# 01_MAIN.net
KiCad netlist of a schematic drawn in Altium Designer
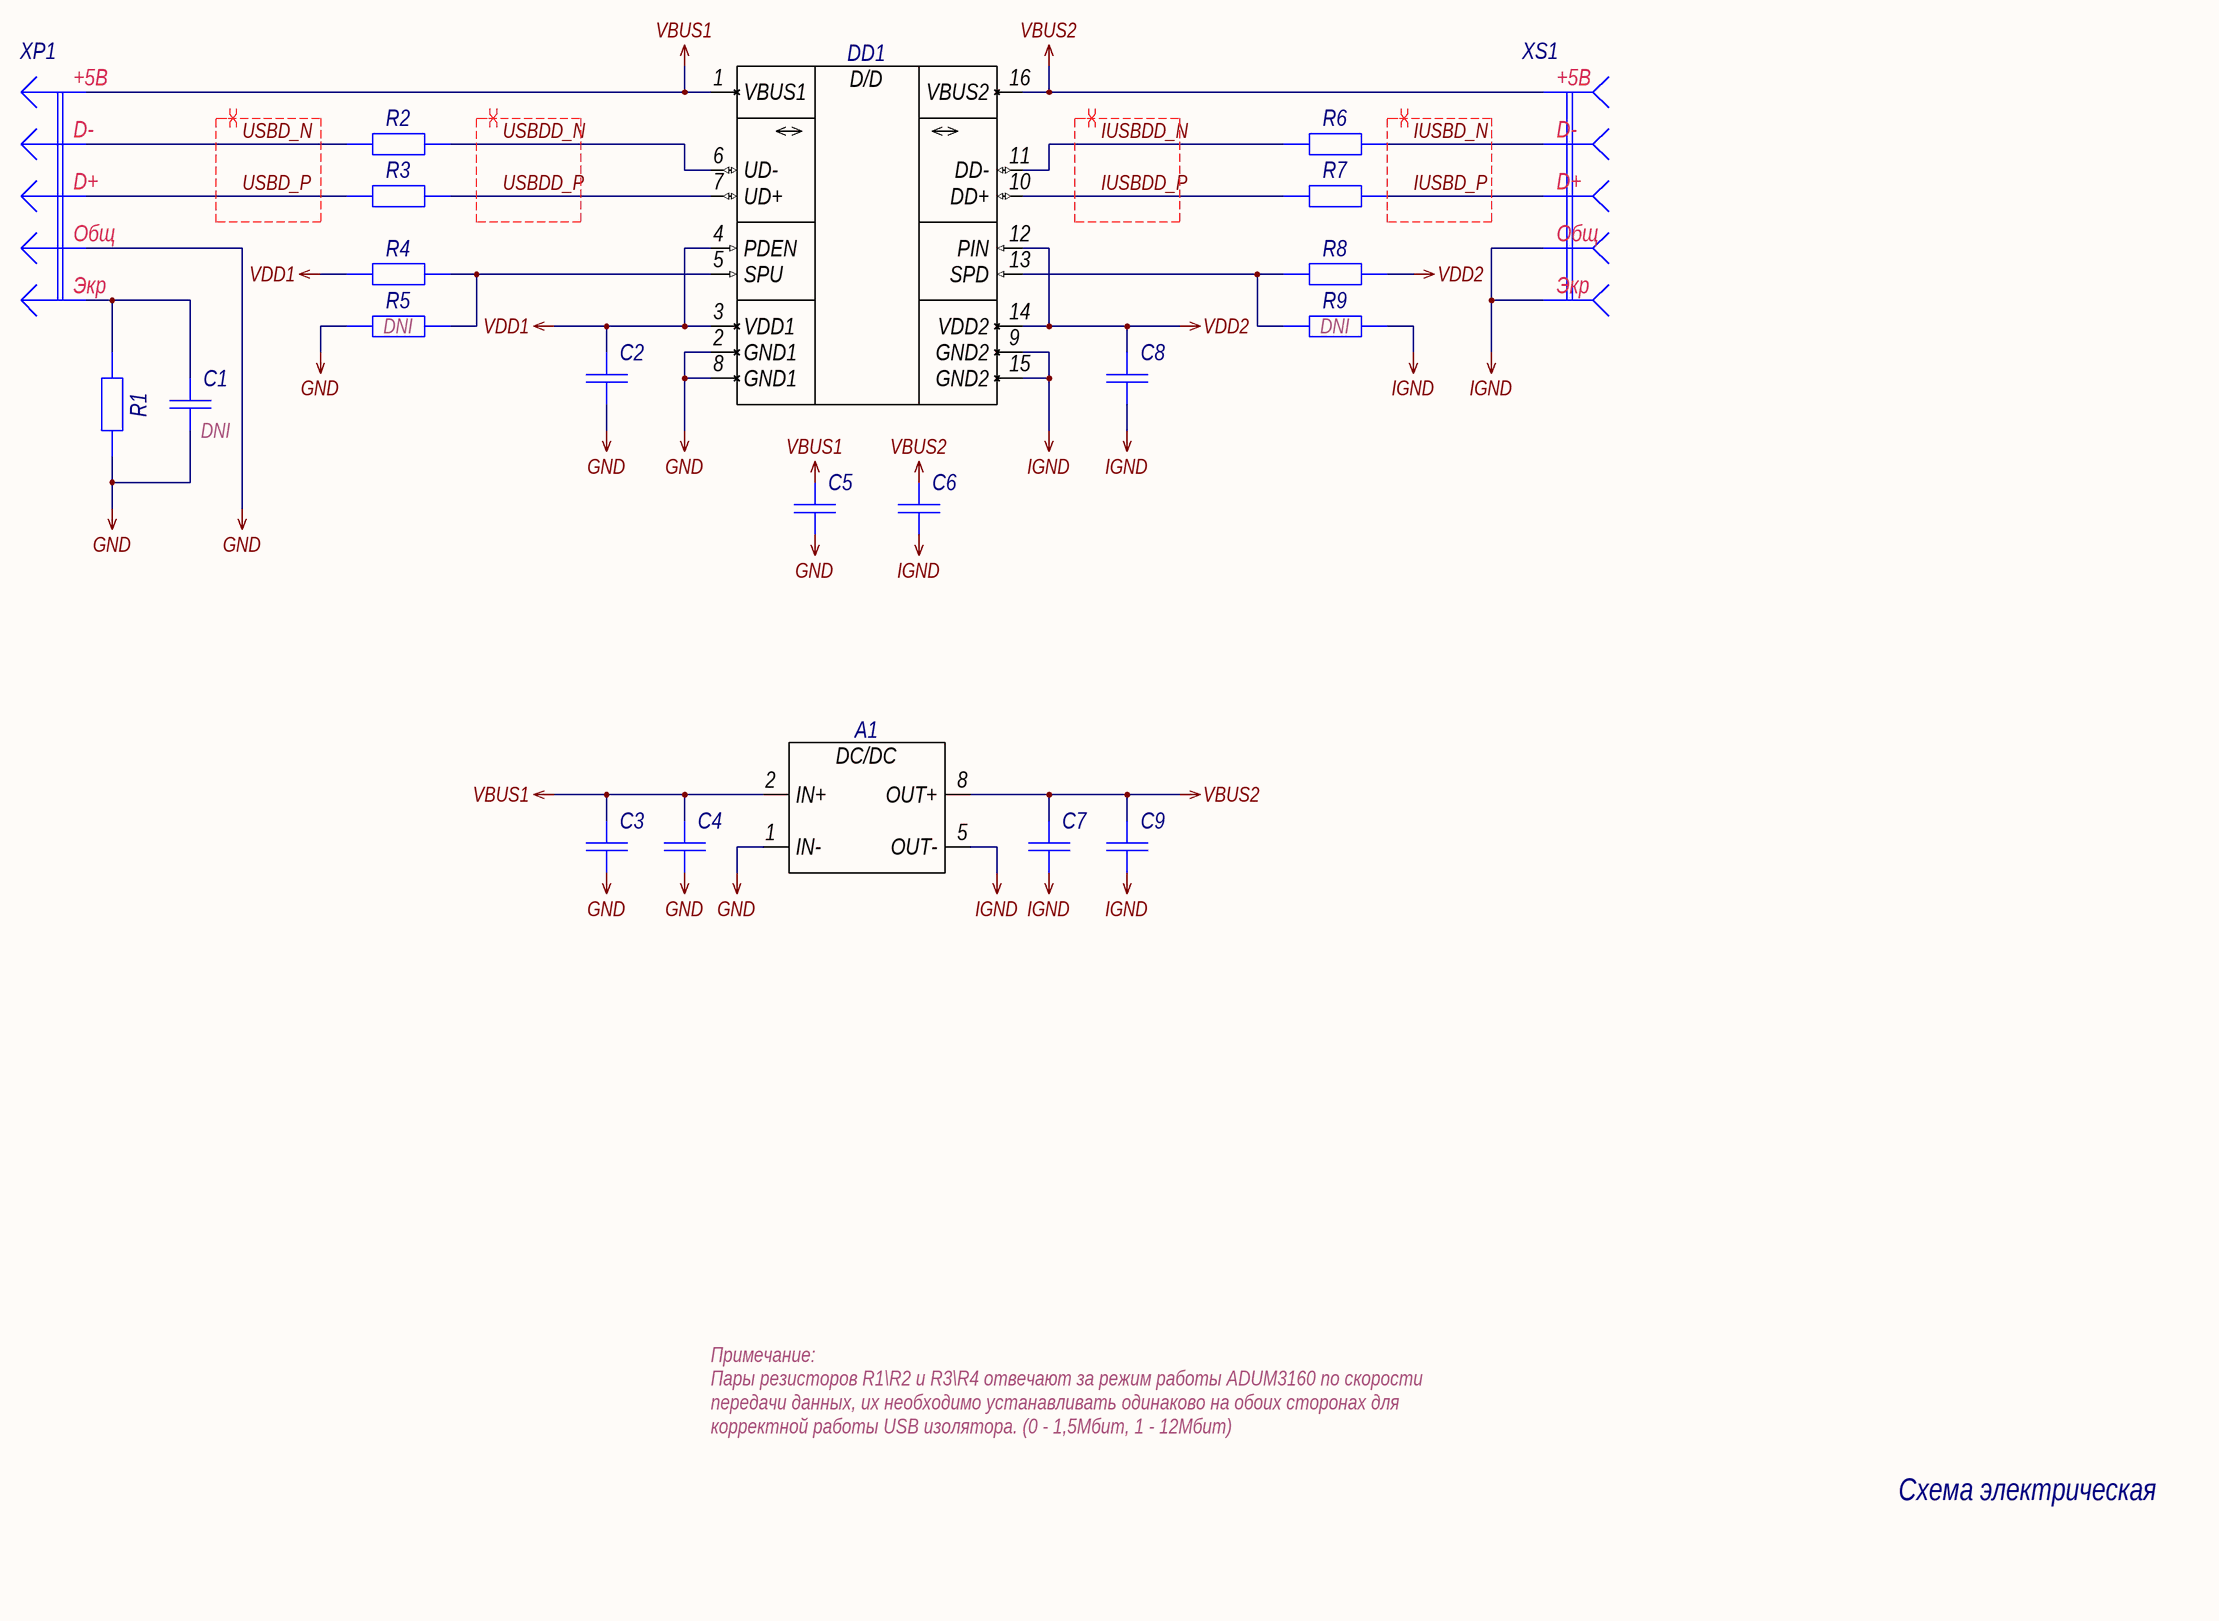
[diagram p0: 01_MAIN.SchDoc]

(export (version "E")
  (design (tool "Eeschema 10.0.6"))
  (components
    (comp (ref "A1")
      (value "AM1L-xxxxSH30-Series")
      (footprint "AM1L-xxxxSH30-Series")
      (fields
        (field (name "PART NUMBER") "AM1L-0505SH30-NZ")
        (field (name "MANUFACTURER") "Aimtec")
        (field (name "PUBLISHER") "Andrew Danich")
      )
      (libsource (lib "ADLib") (part "AM1L-xxxxSH30-Series"))
    )
    (comp (ref "C1")
      (value "Capacitor")
      (footprint "C0603_L")
      (fields
        (field (name "PART NUMBER") "GRM188R72A104KA35D")
        (field (name "VOLTAGE") "100V")
        (field (name "TOLERANCE") "±10%")
        (field (name "PUBLISHER") "Andrew Danich")
      )
      (libsource (lib "ADLib") (part "Capacitor"))
    )
    (comp (ref "C2")
      (value "Capacitor")
      (footprint "C0603_L")
      (fields
        (field (name "PART NUMBER") "GRM188R72A104KA35D")
        (field (name "VOLTAGE") "100V")
        (field (name "TOLERANCE") "±10%")
        (field (name "PUBLISHER") "Andrew Danich")
      )
      (libsource (lib "ADLib") (part "Capacitor"))
    )
    (comp (ref "C3")
      (value "Capacitor")
      (footprint "C0603_L")
      (fields
        (field (name "PART NUMBER") "GRM188R72A104KA35D")
        (field (name "VOLTAGE") "100V")
        (field (name "TOLERANCE") "±10%")
        (field (name "PUBLISHER") "Andrew Danich")
      )
      (libsource (lib "ADLib") (part "Capacitor"))
    )
    (comp (ref "C4")
      (value "Capacitor")
      (footprint "C0603_L")
      (fields
        (field (name "PART NUMBER") "GRM188R61A106KE69D")
        (field (name "VOLTAGE") "10V")
        (field (name "TOLERANCE") "±10%")
        (field (name "PUBLISHER") "Andrew Danich")
      )
      (libsource (lib "ADLib") (part "Capacitor"))
    )
    (comp (ref "C5")
      (value "Capacitor")
      (footprint "C0603_L")
      (fields
        (field (name "PART NUMBER") "GRM188R72A104KA35D")
        (field (name "VOLTAGE") "100V")
        (field (name "TOLERANCE") "±10%")
        (field (name "PUBLISHER") "Andrew Danich")
      )
      (libsource (lib "ADLib") (part "Capacitor"))
    )
    (comp (ref "C6")
      (value "Capacitor")
      (footprint "C0603_L")
      (fields
        (field (name "PART NUMBER") "GRM188R72A104KA35D")
        (field (name "VOLTAGE") "100V")
        (field (name "TOLERANCE") "±10%")
        (field (name "PUBLISHER") "Andrew Danich")
      )
      (libsource (lib "ADLib") (part "Capacitor"))
    )
    (comp (ref "C7")
      (value "Capacitor")
      (footprint "C0603_L")
      (fields
        (field (name "PART NUMBER") "GRM188R61A226ME15D")
        (field (name "VOLTAGE") "10V")
        (field (name "TOLERANCE") "±20%")
        (field (name "PUBLISHER") "Andrew Danich")
      )
      (libsource (lib "ADLib") (part "Capacitor"))
    )
    (comp (ref "C8")
      (value "Capacitor")
      (footprint "C0603_L")
      (fields
        (field (name "PART NUMBER") "GRM188R72A104KA35D")
        (field (name "VOLTAGE") "100V")
        (field (name "TOLERANCE") "±10%")
        (field (name "PUBLISHER") "Andrew Danich")
      )
      (libsource (lib "ADLib") (part "Capacitor"))
    )
    (comp (ref "C9")
      (value "Capacitor")
      (footprint "C0603_L")
      (fields
        (field (name "PART NUMBER") "GRM188R72A104KA35D")
        (field (name "VOLTAGE") "100V")
        (field (name "TOLERANCE") "±10%")
        (field (name "PUBLISHER") "Andrew Danich")
      )
      (libsource (lib "ADLib") (part "Capacitor"))
    )
    (comp (ref "DD1")
      (value "ADuMx160-Series")
      (footprint "SOIC-16_127P1030X750X265_N")
      (fields
        (field (name "PART NUMBER") "ADUM3160BRWZ")
        (field (name "MANUFACTURER") "Analog Devices")
        (field (name "PUBLISHER") "Andrew Danich")
      )
      (libsource (lib "ADLib") (part "ADuMx160-Series"))
    )
    (comp (ref "R1")
      (value "Resistor")
      (footprint "R0603_L")
      (fields
        (field (name "PART NUMBER") "RC0603JR-070R")
        (field (name "TOLERANCE") "±5%")
        (field (name "MANUFACTURER") "Yageo")
        (field (name "PUBLISHER") "Andrew Danich")
      )
      (libsource (lib "ADLib") (part "Resistor"))
    )
    (comp (ref "R2")
      (value "Resistor")
      (footprint "R0603_L")
      (fields
        (field (name "PART NUMBER") "RC0603JR-0722RL")
        (field (name "TOLERANCE") "±5%")
        (field (name "MANUFACTURER") "Yageo")
        (field (name "PUBLISHER") "Andrew Danich")
      )
      (libsource (lib "ADLib") (part "Resistor"))
    )
    (comp (ref "R3")
      (value "Resistor")
      (footprint "R0603_L")
      (fields
        (field (name "PART NUMBER") "RC0603JR-0722RL")
        (field (name "TOLERANCE") "±5%")
        (field (name "MANUFACTURER") "Yageo")
        (field (name "PUBLISHER") "Andrew Danich")
      )
      (libsource (lib "ADLib") (part "Resistor"))
    )
    (comp (ref "R4")
      (value "Resistor")
      (footprint "R0603_L")
      (fields
        (field (name "PART NUMBER") "RC0603JR-070R")
        (field (name "TOLERANCE") "±5%")
        (field (name "MANUFACTURER") "Yageo")
        (field (name "PUBLISHER") "Andrew Danich")
      )
      (libsource (lib "ADLib") (part "Resistor"))
    )
    (comp (ref "R5")
      (value "Resistor")
      (footprint "R0603_L")
      (fields
        (field (name "PART NUMBER") "RC0603JR-070R")
        (field (name "TOLERANCE") "±5%")
        (field (name "MANUFACTURER") "Yageo")
        (field (name "PUBLISHER") "Andrew Danich")
      )
      (libsource (lib "ADLib") (part "Resistor"))
    )
    (comp (ref "R6")
      (value "Resistor")
      (footprint "R0603_L")
      (fields
        (field (name "PART NUMBER") "RC0603JR-0722RL")
        (field (name "TOLERANCE") "±5%")
        (field (name "MANUFACTURER") "Yageo")
        (field (name "PUBLISHER") "Andrew Danich")
      )
      (libsource (lib "ADLib") (part "Resistor"))
    )
    (comp (ref "R7")
      (value "Resistor")
      (footprint "R0603_L")
      (fields
        (field (name "PART NUMBER") "RC0603JR-0722RL")
        (field (name "TOLERANCE") "±5%")
        (field (name "MANUFACTURER") "Yageo")
        (field (name "PUBLISHER") "Andrew Danich")
      )
      (libsource (lib "ADLib") (part "Resistor"))
    )
    (comp (ref "R8")
      (value "Resistor")
      (footprint "R0603_L")
      (fields
        (field (name "PART NUMBER") "RC0603JR-070R")
        (field (name "TOLERANCE") "±5%")
        (field (name "MANUFACTURER") "Yageo")
        (field (name "PUBLISHER") "Andrew Danich")
      )
      (libsource (lib "ADLib") (part "Resistor"))
    )
    (comp (ref "R9")
      (value "Resistor")
      (footprint "R0603_L")
      (fields
        (field (name "PART NUMBER") "RC0603JR-070R")
        (field (name "TOLERANCE") "±5%")
        (field (name "MANUFACTURER") "Yageo")
        (field (name "PUBLISHER") "Andrew Danich")
      )
      (libsource (lib "ADLib") (part "Resistor"))
    )
    (comp (ref "XP1")
      (value "HOST")
      (footprint "DS1097")
      (fields
        (field (name "PART NUMBER") "DS1097-B")
        (field (name "MANUFACTURER") "Connfly Electronic Co., Ltd")
        (field (name "PUBLISHER") "Andrew Danich")
      )
      (libsource (lib "ADLib") (part "Con-5-M-USB"))
    )
    (comp (ref "XS1")
      (value "DEVICE")
      (footprint "2041335-1")
      (fields
        (field (name "PART NUMBER") "2041335-1")
        (field (name "MANUFACTURER") "TE Connectivity")
        (field (name "PUBLISHER") "Andrew Danich")
      )
      (libsource (lib "ADLib") (part "Con-5-F-USB"))
    )
  )
  (nets
    (net (code "1") (name "/IUSBDD_N") (class "Default")
      (node (ref "DD1") (pin "11") (pinfunction "DD-_11") (pintype "bidirectional"))
      (node (ref "R6") (pin "1") (pinfunction "1_1") (pintype "passive"))
    )
    (net (code "2") (name "/IUSBDD_P") (class "Default")
      (node (ref "DD1") (pin "10") (pinfunction "DD+_10") (pintype "bidirectional"))
      (node (ref "R7") (pin "1") (pinfunction "1_1") (pintype "passive"))
    )
    (net (code "3") (name "/IUSBD_N") (class "Default")
      (node (ref "R6") (pin "2") (pinfunction "2_2") (pintype "passive"))
      (node (ref "XS1") (pin "2") (pintype "passive"))
    )
    (net (code "4") (name "/IUSBD_P") (class "Default")
      (node (ref "R7") (pin "2") (pinfunction "2_2") (pintype "passive"))
      (node (ref "XS1") (pin "3") (pintype "passive"))
    )
    (net (code "5") (name "/USBDD_N") (class "Default")
      (node (ref "DD1") (pin "6") (pinfunction "UD-_6") (pintype "bidirectional"))
      (node (ref "R2") (pin "2") (pinfunction "2_2") (pintype "passive"))
    )
    (net (code "6") (name "/USBDD_P") (class "Default")
      (node (ref "DD1") (pin "7") (pinfunction "UD+_7") (pintype "bidirectional"))
      (node (ref "R3") (pin "2") (pinfunction "2_2") (pintype "passive"))
    )
    (net (code "7") (name "/USBD_N") (class "Default")
      (node (ref "R2") (pin "1") (pinfunction "1_1") (pintype "passive"))
      (node (ref "XP1") (pin "2") (pintype "passive"))
    )
    (net (code "8") (name "/USBD_P") (class "Default")
      (node (ref "R3") (pin "1") (pinfunction "1_1") (pintype "passive"))
      (node (ref "XP1") (pin "3") (pintype "passive"))
    )
    (net (code "9") (name "GND") (class "Default")
      (node (ref "A1") (pin "1") (pinfunction "IN-_1") (pintype "power_in"))
      (node (ref "C1") (pin "1") (pinfunction "1_1") (pintype "passive"))
      (node (ref "C2") (pin "1") (pinfunction "1_1") (pintype "passive"))
      (node (ref "C3") (pin "1") (pinfunction "1_1") (pintype "passive"))
      (node (ref "C4") (pin "1") (pinfunction "1_1") (pintype "passive"))
      (node (ref "C5") (pin "1") (pinfunction "1_1") (pintype "passive"))
      (node (ref "DD1") (pin "2") (pinfunction "GND1_2") (pintype "power_in"))
      (node (ref "DD1") (pin "8") (pinfunction "GND1_8") (pintype "power_in"))
      (node (ref "R1") (pin "1") (pinfunction "1_1") (pintype "passive"))
      (node (ref "R5") (pin "2") (pinfunction "2_2") (pintype "passive"))
      (node (ref "XP1") (pin "4") (pintype "passive"))
    )
    (net (code "10") (name "IGND") (class "Default")
      (node (ref "A1") (pin "5") (pinfunction "OUT-_5") (pintype "power_in"))
      (node (ref "C6") (pin "1") (pinfunction "1_1") (pintype "passive"))
      (node (ref "C7") (pin "1") (pinfunction "1_1") (pintype "passive"))
      (node (ref "C8") (pin "1") (pinfunction "1_1") (pintype "passive"))
      (node (ref "C9") (pin "1") (pinfunction "1_1") (pintype "passive"))
      (node (ref "DD1") (pin "15") (pinfunction "GND2_15") (pintype "power_in"))
      (node (ref "DD1") (pin "9") (pinfunction "GND2_9") (pintype "power_in"))
      (node (ref "R9") (pin "1") (pinfunction "1_1") (pintype "passive"))
      (node (ref "XS1") (pin "4") (pintype "passive"))
      (node (ref "XS1") (pin "5") (pintype "passive"))
    )
    (net (code "11") (name "Net-(C1-Pad2)") (class "Default")
      (node (ref "C1") (pin "2") (pinfunction "2_2") (pintype "passive"))
      (node (ref "R1") (pin "2") (pinfunction "2_2") (pintype "passive"))
      (node (ref "XP1") (pin "5") (pintype "passive"))
    )
    (net (code "12") (name "Net-(DD1-SPD)") (class "Default")
      (node (ref "DD1") (pin "13") (pinfunction "SPD_13") (pintype "input"))
      (node (ref "R8") (pin "2") (pinfunction "2_2") (pintype "passive"))
      (node (ref "R9") (pin "2") (pinfunction "2_2") (pintype "passive"))
    )
    (net (code "13") (name "Net-(DD1-SPU)") (class "Default")
      (node (ref "DD1") (pin "5") (pinfunction "SPU_5") (pintype "input"))
      (node (ref "R4") (pin "1") (pinfunction "1_1") (pintype "passive"))
      (node (ref "R5") (pin "1") (pinfunction "1_1") (pintype "passive"))
    )
    (net (code "14") (name "VBUS1") (class "Default")
      (node (ref "A1") (pin "2") (pinfunction "IN+_2") (pintype "power_in"))
      (node (ref "C3") (pin "2") (pinfunction "2_2") (pintype "passive"))
      (node (ref "C4") (pin "2") (pinfunction "2_2") (pintype "passive"))
      (node (ref "C5") (pin "2") (pinfunction "2_2") (pintype "passive"))
      (node (ref "DD1") (pin "1") (pinfunction "VBUS1_1") (pintype "power_in"))
      (node (ref "XP1") (pin "1") (pintype "passive"))
    )
    (net (code "15") (name "VBUS2") (class "Default")
      (node (ref "A1") (pin "8") (pinfunction "OUT+_8") (pintype "power_in"))
      (node (ref "C6") (pin "2") (pinfunction "2_2") (pintype "passive"))
      (node (ref "C7") (pin "2") (pinfunction "2_2") (pintype "passive"))
      (node (ref "C9") (pin "2") (pinfunction "2_2") (pintype "passive"))
      (node (ref "DD1") (pin "16") (pinfunction "VBUS2_16") (pintype "power_in"))
      (node (ref "XS1") (pin "1") (pintype "passive"))
    )
    (net (code "16") (name "VDD1") (class "Default")
      (node (ref "C2") (pin "2") (pinfunction "2_2") (pintype "passive"))
      (node (ref "DD1") (pin "3") (pinfunction "VDD1_3") (pintype "power_in"))
      (node (ref "DD1") (pin "4") (pinfunction "PDEN_4") (pintype "input"))
      (node (ref "R4") (pin "2") (pinfunction "2_2") (pintype "passive"))
    )
    (net (code "17") (name "VDD2") (class "Default")
      (node (ref "C8") (pin "2") (pinfunction "2_2") (pintype "passive"))
      (node (ref "DD1") (pin "12") (pinfunction "PIN_12") (pintype "input"))
      (node (ref "DD1") (pin "14") (pinfunction "VDD2_14") (pintype "power_in"))
      (node (ref "R8") (pin "1") (pinfunction "1_1") (pintype "passive"))
    )
  )
)
